# chess_module_connectors.net
KiCad netlist of a schematic drawn in Altium Designer
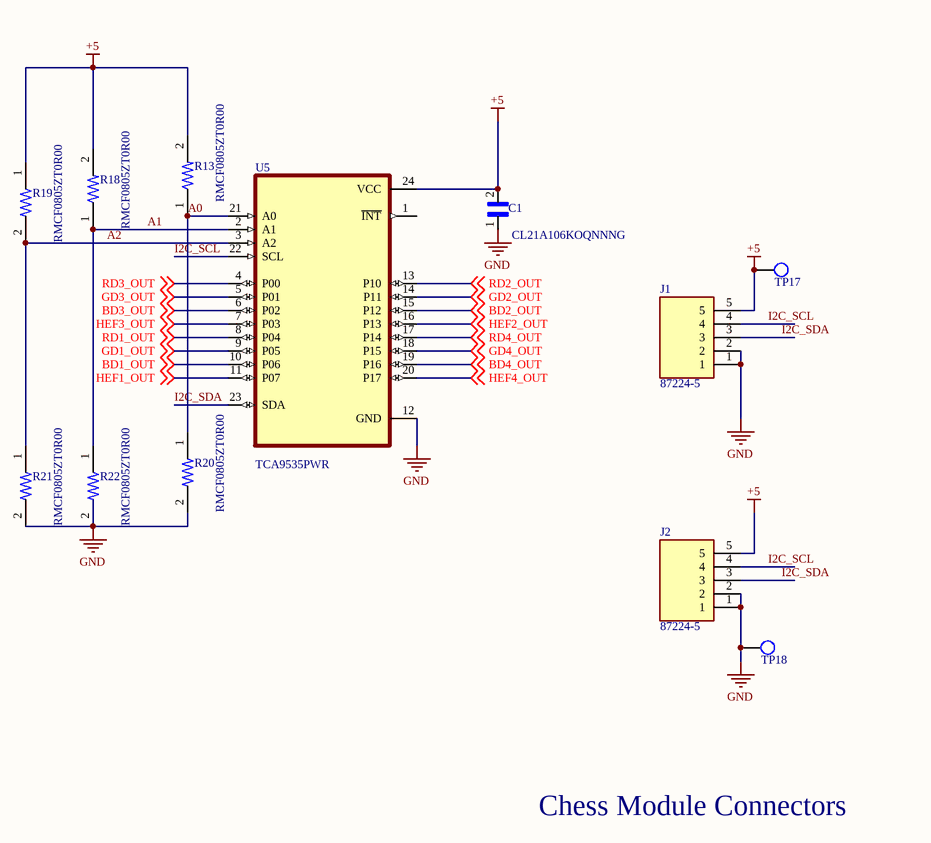
[diagram p0: chess_module_connectors.SchDoc]

(export (version "E")
  (design (tool "Eeschema 10.0.6"))
  (components
    (comp (ref "C1")
      (value "CL21A106KOQNNNG")
      (footprint "CAPC2012X140N")
      (description "10ÂµF Â±10% 16V Ceramic Capacitor X5R 0805 _2012 Metric_")
      (fields
        (field (name "MF") "Samsung Electro-Mechanics")
        (field (name "DIGI-KEY_PART_NUMBER") "1276-6455-1-ND")
      )
      (libsource (lib "base-board") (part "CL21A106KOQNNNG"))
    )
    (comp (ref "J1")
      (value "87224-5")
      (footprint "TE_87224-5")
      (description "Conn Unshrouded Header HDR 5 POS 2.54mm Solder ST Thru-Hole")
      (fields (field (name "MF") "TE Connectivity"))
      (libsource (lib "chess_module") (part "87224-5"))
    )
    (comp (ref "J2")
      (value "87224-5")
      (footprint "TE_87224-5")
      (description "Conn Unshrouded Header HDR 5 POS 2.54mm Solder ST Thru-Hole")
      (fields (field (name "MF") "TE Connectivity"))
      (libsource (lib "chess_module") (part "87224-5"))
    )
    (comp (ref "R13")
      (value "RMCF0805ZT0R00")
      (footprint "RESC2012X60N")
      (description "0 Ohms Jumper 0.125W, 1/8W Chip Resistor 0805 (2012 Metric) Automotive AEC-Q200 Thick Film")
      (fields (field (name "MF") "Stackpole Electronics"))
      (libsource (lib "base-board") (part "RMCF0805ZT0R00"))
    )
    (comp (ref "R18")
      (value "RMCF0805ZT0R00")
      (footprint "RESC2012X60N")
      (description "0 Ohms Jumper 0.125W, 1/8W Chip Resistor 0805 (2012 Metric) Automotive AEC-Q200 Thick Film")
      (fields (field (name "MF") "Stackpole Electronics"))
      (libsource (lib "base-board") (part "RMCF0805ZT0R00"))
    )
    (comp (ref "R19")
      (value "RMCF0805ZT0R00")
      (footprint "RESC2012X60N")
      (description "0 Ohms Jumper 0.125W, 1/8W Chip Resistor 0805 (2012 Metric) Automotive AEC-Q200 Thick Film")
      (fields (field (name "MF") "Stackpole Electronics"))
      (libsource (lib "base-board") (part "RMCF0805ZT0R00"))
    )
    (comp (ref "R20")
      (value "RMCF0805ZT0R00")
      (footprint "RESC2012X60N")
      (description "0 Ohms Jumper 0.125W, 1/8W Chip Resistor 0805 (2012 Metric) Automotive AEC-Q200 Thick Film")
      (fields (field (name "MF") "Stackpole Electronics"))
      (libsource (lib "base-board") (part "RMCF0805ZT0R00"))
    )
    (comp (ref "R21")
      (value "RMCF0805ZT0R00")
      (footprint "RESC2012X60N")
      (description "0 Ohms Jumper 0.125W, 1/8W Chip Resistor 0805 (2012 Metric) Automotive AEC-Q200 Thick Film")
      (fields (field (name "MF") "Stackpole Electronics"))
      (libsource (lib "base-board") (part "RMCF0805ZT0R00"))
    )
    (comp (ref "R22")
      (value "RMCF0805ZT0R00")
      (footprint "RESC2012X60N")
      (description "0 Ohms Jumper 0.125W, 1/8W Chip Resistor 0805 (2012 Metric) Automotive AEC-Q200 Thick Film")
      (fields (field (name "MF") "Stackpole Electronics"))
      (libsource (lib "base-board") (part "RMCF0805ZT0R00"))
    )
    (comp (ref "TP17")
      (value "TP_1206")
      (footprint "TP-SMC-1206")
      (description "Test Point SMD 1206")
      (fields
        (field (name "MANUFACTURER") "TE Connectivity (Tyco Electronics)")
        (field (name "MANUFACTURER PART NUMBER") "1625854-1")
      )
      (libsource (lib "base-board") (part "TP_1206"))
    )
    (comp (ref "TP18")
      (value "TP_1206")
      (footprint "TP-SMC-1206")
      (description "Test Point SMD 1206")
      (fields
        (field (name "MANUFACTURER") "TE Connectivity (Tyco Electronics)")
        (field (name "MANUFACTURER PART NUMBER") "1625854-1")
      )
      (libsource (lib "base-board") (part "TP_1206"))
    )
    (comp (ref "U5")
      (value "TCA9535PWR")
      (footprint "SOP65P640X120-24N")
      (fields (field (name "MF") "Texas Instruments"))
      (libsource (lib "base-board") (part "TCA9535PWR"))
    )
  )
  (nets
    (net (code "1") (name "+5") (class "Default")
      (node (ref "C1") (pin "2") (pinfunction "2_2") (pintype "passive"))
      (node (ref "J1") (pin "5") (pinfunction "5_5") (pintype "passive"))
      (node (ref "J2") (pin "5") (pinfunction "5_5") (pintype "passive"))
      (node (ref "R13") (pin "2") (pinfunction "2_2") (pintype "passive"))
      (node (ref "R18") (pin "2") (pinfunction "2_2") (pintype "passive"))
      (node (ref "R19") (pin "1") (pinfunction "1_1") (pintype "passive"))
      (node (ref "TP17") (pin "1") (pintype "passive"))
      (node (ref "U5") (pin "24") (pinfunction "VCC_24") (pintype "power_in"))
    )
    (net (code "2") (name "/A0") (class "Default")
      (node (ref "R13") (pin "1") (pinfunction "1_1") (pintype "passive"))
      (node (ref "R20") (pin "1") (pinfunction "1_1") (pintype "passive"))
      (node (ref "U5") (pin "21") (pinfunction "A0_21") (pintype "input"))
    )
    (net (code "3") (name "/A1") (class "Default")
      (node (ref "R18") (pin "1") (pinfunction "1_1") (pintype "passive"))
      (node (ref "R22") (pin "1") (pinfunction "1_1") (pintype "passive"))
      (node (ref "U5") (pin "2") (pinfunction "A1_2") (pintype "input"))
    )
    (net (code "4") (name "/A2") (class "Default")
      (node (ref "R19") (pin "2") (pinfunction "2_2") (pintype "passive"))
      (node (ref "R21") (pin "1") (pinfunction "1_1") (pintype "passive"))
      (node (ref "U5") (pin "3") (pinfunction "A2_3") (pintype "input"))
    )
    (net (code "5") (name "/I2C_SCL") (class "Default")
      (node (ref "J1") (pin "4") (pinfunction "4_4") (pintype "passive"))
      (node (ref "J2") (pin "4") (pinfunction "4_4") (pintype "passive"))
      (node (ref "U5") (pin "22") (pinfunction "SCL_22") (pintype "input"))
    )
    (net (code "6") (name "/I2C_SDA") (class "Default")
      (node (ref "J1") (pin "3") (pinfunction "3_3") (pintype "passive"))
      (node (ref "J2") (pin "3") (pinfunction "3_3") (pintype "passive"))
      (node (ref "U5") (pin "23") (pinfunction "SDA_23") (pintype "bidirectional"))
    )
    (net (code "7") (name "BD1_OUT") (class "Default")
      (node (ref "U5") (pin "10") (pinfunction "P06_10") (pintype "bidirectional"))
    )
    (net (code "8") (name "BD2_OUT") (class "Default")
      (node (ref "U5") (pin "15") (pinfunction "P12_15") (pintype "bidirectional"))
    )
    (net (code "9") (name "BD3_OUT") (class "Default")
      (node (ref "U5") (pin "6") (pinfunction "P02_6") (pintype "bidirectional"))
    )
    (net (code "10") (name "BD4_OUT") (class "Default")
      (node (ref "U5") (pin "19") (pinfunction "P16_19") (pintype "bidirectional"))
    )
    (net (code "11") (name "GD1_OUT") (class "Default")
      (node (ref "U5") (pin "9") (pinfunction "P05_9") (pintype "bidirectional"))
    )
    (net (code "12") (name "GD2_OUT") (class "Default")
      (node (ref "U5") (pin "14") (pinfunction "P11_14") (pintype "bidirectional"))
    )
    (net (code "13") (name "GD3_OUT") (class "Default")
      (node (ref "U5") (pin "5") (pinfunction "P01_5") (pintype "bidirectional"))
    )
    (net (code "14") (name "GD4_OUT") (class "Default")
      (node (ref "U5") (pin "18") (pinfunction "P15_18") (pintype "bidirectional"))
    )
    (net (code "15") (name "GND") (class "Default")
      (node (ref "C1") (pin "1") (pinfunction "1_1") (pintype "passive"))
      (node (ref "J1") (pin "1") (pinfunction "1_1") (pintype "passive"))
      (node (ref "J1") (pin "2") (pinfunction "2_2") (pintype "passive"))
      (node (ref "J2") (pin "1") (pinfunction "1_1") (pintype "passive"))
      (node (ref "J2") (pin "2") (pinfunction "2_2") (pintype "passive"))
      (node (ref "R20") (pin "2") (pinfunction "2_2") (pintype "passive"))
      (node (ref "R21") (pin "2") (pinfunction "2_2") (pintype "passive"))
      (node (ref "R22") (pin "2") (pinfunction "2_2") (pintype "passive"))
      (node (ref "TP18") (pin "1") (pintype "passive"))
      (node (ref "U5") (pin "12") (pinfunction "GND_12") (pintype "power_in"))
    )
    (net (code "16") (name "HEF1_OUT") (class "Default")
      (node (ref "U5") (pin "11") (pinfunction "P07_11") (pintype "bidirectional"))
    )
    (net (code "17") (name "HEF2_OUT") (class "Default")
      (node (ref "U5") (pin "16") (pinfunction "P13_16") (pintype "bidirectional"))
    )
    (net (code "18") (name "HEF3_OUT") (class "Default")
      (node (ref "U5") (pin "7") (pinfunction "P03_7") (pintype "bidirectional"))
    )
    (net (code "19") (name "HEF4_OUT") (class "Default")
      (node (ref "U5") (pin "20") (pinfunction "P17_20") (pintype "bidirectional"))
    )
    (net (code "20") (name "RD1_OUT") (class "Default")
      (node (ref "U5") (pin "8") (pinfunction "P04_8") (pintype "bidirectional"))
    )
    (net (code "21") (name "RD2_OUT") (class "Default")
      (node (ref "U5") (pin "13") (pinfunction "P10_13") (pintype "bidirectional"))
    )
    (net (code "22") (name "RD3_OUT") (class "Default")
      (node (ref "U5") (pin "4") (pinfunction "P00_4") (pintype "bidirectional"))
    )
    (net (code "23") (name "RD4_OUT") (class "Default")
      (node (ref "U5") (pin "17") (pinfunction "P14_17") (pintype "bidirectional"))
    )
    (net (code "24") (name "unconnected-(U5-~{INT}-Pad1)") (class "Default")
      (node (ref "U5") (pin "1") (pinfunction "~{INT}_1") (pintype "output"))
    )
  )
)
